# POWER.net
KiCad netlist of a schematic drawn in Altium Designer
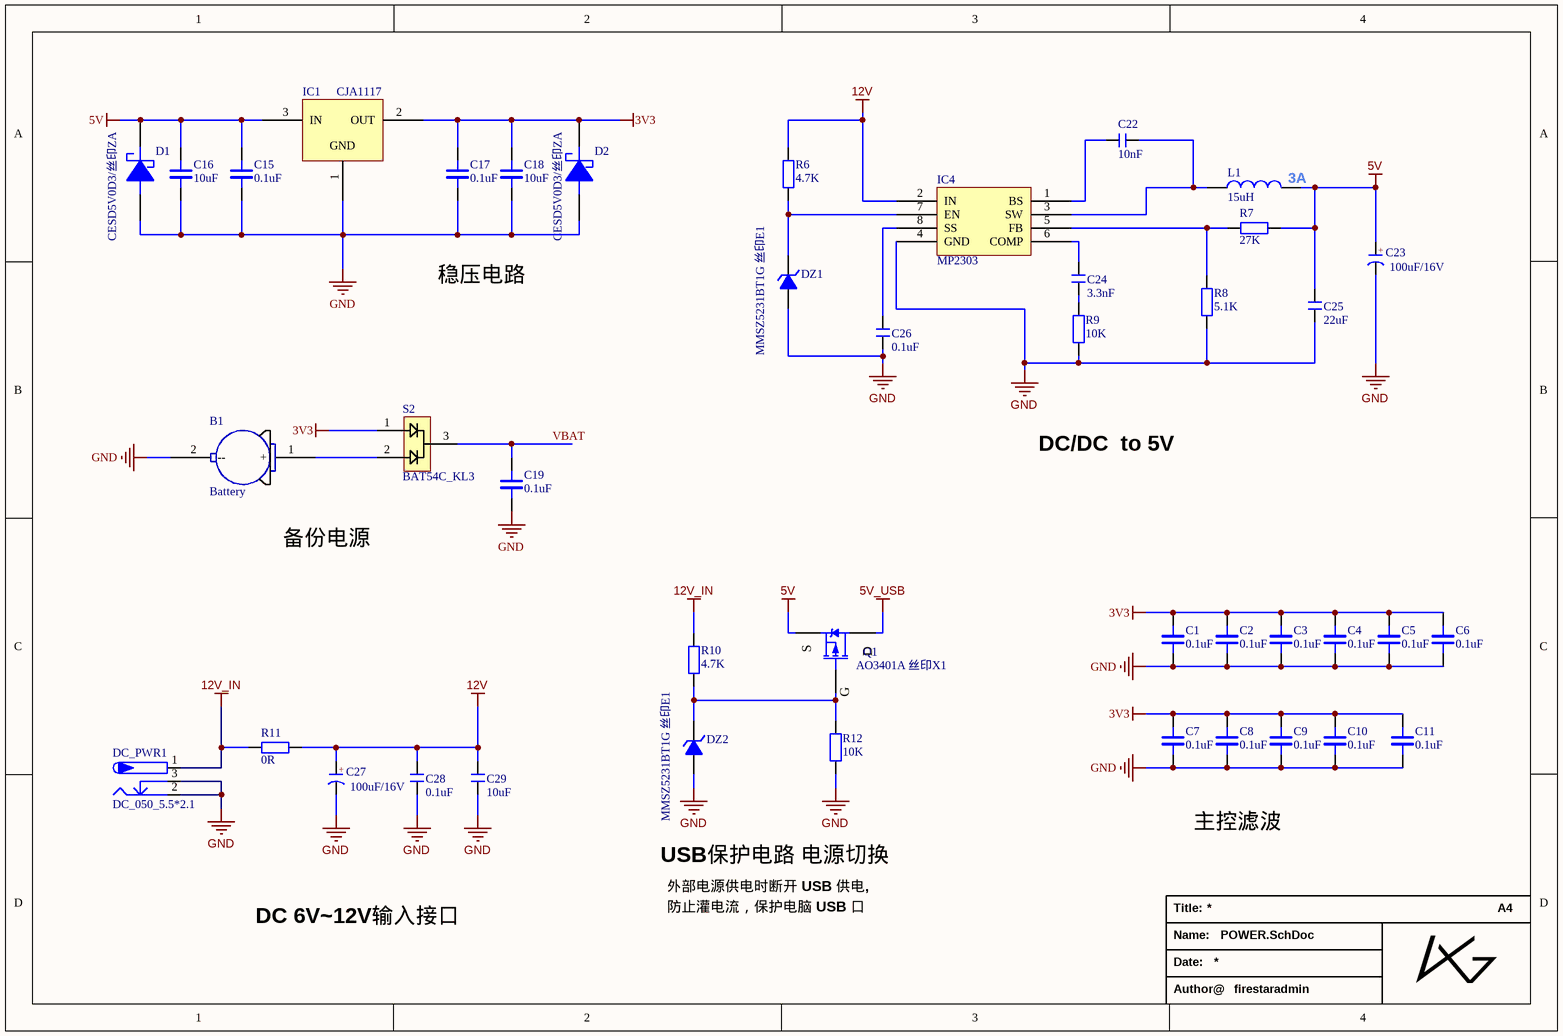
[diagram p0: POWER.SchDoc]

(export (version "E")
  (design (tool "Eeschema 10.0.6"))
  (components
    (comp (ref "B1")
      (value "Battery")
      (footprint "CR1220_B")
      (libsource (lib "altium-import") (part "root_2_Battery_"))
    )
    (comp (ref "C1")
      (value "0.1uF")
      (footprint "C 0603_M")
      (description "Capacitor")
      (libsource (lib "General") (part "CAP"))
    )
    (comp (ref "C2")
      (value "0.1uF")
      (footprint "C 0603_M")
      (description "Capacitor")
      (libsource (lib "General") (part "CAP"))
    )
    (comp (ref "C3")
      (value "0.1uF")
      (footprint "C 0603_M")
      (description "Capacitor")
      (libsource (lib "General") (part "CAP"))
    )
    (comp (ref "C4")
      (value "0.1uF")
      (footprint "C 0603_M")
      (description "Capacitor")
      (libsource (lib "General") (part "CAP"))
    )
    (comp (ref "C5")
      (value "0.1uF")
      (footprint "C 0603_M")
      (description "Capacitor")
      (libsource (lib "General") (part "CAP"))
    )
    (comp (ref "C6")
      (value "0.1uF")
      (footprint "C 0603_M")
      (description "Capacitor")
      (libsource (lib "General") (part "CAP"))
    )
    (comp (ref "C7")
      (value "0.1uF")
      (footprint "C 0603_M")
      (description "Capacitor")
      (libsource (lib "General") (part "CAP"))
    )
    (comp (ref "C8")
      (value "0.1uF")
      (footprint "C 0603_M")
      (description "Capacitor")
      (libsource (lib "General") (part "CAP"))
    )
    (comp (ref "C9")
      (value "0.1uF")
      (footprint "C 0603_M")
      (description "Capacitor")
      (libsource (lib "General") (part "CAP"))
    )
    (comp (ref "C10")
      (value "0.1uF")
      (footprint "C 0603_M")
      (description "Capacitor")
      (libsource (lib "General") (part "CAP"))
    )
    (comp (ref "C11")
      (value "0.1uF")
      (footprint "C 0603_M")
      (description "Capacitor")
      (libsource (lib "General") (part "CAP"))
    )
    (comp (ref "C15")
      (value "0.1uF")
      (footprint "C 0603_M")
      (description "Capacitor")
      (libsource (lib "General") (part "CAP"))
    )
    (comp (ref "C16")
      (value "10uF")
      (footprint "C 0603_M")
      (description "Capacitor")
      (libsource (lib "General") (part "CAP"))
    )
    (comp (ref "C17")
      (value "0.1uF")
      (footprint "C 0603_M")
      (description "Capacitor")
      (libsource (lib "General") (part "CAP"))
    )
    (comp (ref "C18")
      (value "10uF")
      (footprint "C 0603_M")
      (description "Capacitor")
      (libsource (lib "General") (part "CAP"))
    )
    (comp (ref "C19")
      (value "0.1uF")
      (footprint "C 0603_M")
      (description "Capacitor")
      (libsource (lib "General") (part "CAP"))
    )
    (comp (ref "C22")
      (value "10nF")
      (footprint "C 0603_M")
      (description "无极性贴片电容")
      (fields (field (name "版权归属") "源创客"))
      (libsource (lib "altium-import") (part "root_2_C_"))
    )
    (comp (ref "C23")
      (value "100uF/16V")
      (footprint "CM D(6.3*5.4)")
      (description "贴片电解电容")
      (fields (field (name "版权归属") "源创客"))
      (libsource (lib "altium-import") (part "root_3_C-CM_"))
    )
    (comp (ref "C24")
      (value "3.3nF")
      (footprint "C 0603_M")
      (description "无极性贴片电容")
      (fields (field (name "版权归属") "源创客"))
      (libsource (lib "altium-import") (part "root_1_C_"))
    )
    (comp (ref "C25")
      (value "22uF")
      (footprint "C 0603_M")
      (description "无极性贴片电容")
      (fields (field (name "版权归属") "源创客"))
      (libsource (lib "altium-import") (part "root_1_C_"))
    )
    (comp (ref "C26")
      (value "0.1uF")
      (footprint "C 0603_M")
      (description "无极性贴片电容")
      (fields (field (name "版权归属") "源创客"))
      (libsource (lib "altium-import") (part "root_1_C_"))
    )
    (comp (ref "C27")
      (value "100uF/16V")
      (footprint "CM D(6.3*5.4)")
      (description "贴片电解电容")
      (fields (field (name "版权归属") "源创客"))
      (libsource (lib "altium-import") (part "root_3_C-CM_"))
    )
    (comp (ref "C28")
      (value "0.1uF")
      (footprint "C 0603_M")
      (description "无极性贴片电容")
      (fields (field (name "版权归属") "源创客"))
      (libsource (lib "altium-import") (part "root_1_C_"))
    )
    (comp (ref "C29")
      (value "10uF")
      (footprint "C 0603_M")
      (description "无极性贴片电容")
      (fields (field (name "版权归属") "源创客"))
      (libsource (lib "altium-import") (part "root_1_C_"))
    )
    (comp (ref "D1")
      (value "CESD5V0D3/丝印ZA")
      (footprint "SOD-323")
      (libsource (lib "altium-import") (part "root_3_TVS_"))
    )
    (comp (ref "D2")
      (value "CESD5V0D3/丝印ZA")
      (footprint "SOD-323")
      (libsource (lib "altium-import") (part "root_3_TVS_"))
    )
    (comp (ref "DC_PWR1")
      (value "DC_050_5.5*2.1")
      (footprint "DC-050")
      (description "低压电源接口")
      (fields (field (name "版权归属") "源创客"))
      (libsource (lib "altium-import") (part "root_0_mirrored_P-DC_"))
    )
    (comp (ref "DZ1")
      (value "MMSZ5231BT1G 丝印E1")
      (footprint "SOD-123")
      (description "5.1V/0.5W稳压管")
      (fields (field (name "版权归属") "源创客"))
      (libsource (lib "altium-import") (part "root_0_1N4625_"))
    )
    (comp (ref "DZ2")
      (value "MMSZ5231BT1G 丝印E1")
      (footprint "SOD-123")
      (description "5.1V/0.5W稳压管")
      (fields (field (name "版权归属") "源创客"))
      (libsource (lib "altium-import") (part "root_0_1N4625_"))
    )
    (comp (ref "IC1")
      (value "CJA1117")
      (footprint "SOT89_M")
      (libsource (lib "altium-import") (part "root_0_CJA1117_"))
    )
    (comp (ref "IC4")
      (value "MP2303")
      (footprint "SOP8_M")
      (libsource (lib "altium-import") (part "root_0_MP2303_"))
    )
    (comp (ref "L1")
      (value "15uH")
      (footprint "L-SMD-0630")
      (description "小功率贴片电感")
      (fields (field (name "版权归属") "源创客"))
      (libsource (lib "3.1   - 电阻-电容-电感") (part "L"))
    )
    (comp (ref "Q1")
      (value "AO3401A 丝印X1")
      (footprint "SOT23-3M")
      (description "P沟道场效应管")
      (fields (field (name "版权归属") "源创客"))
      (libsource (lib "altium-import") (part "root_1_mirrored_SI2301_"))
    )
    (comp (ref "R6")
      (value "4.7K")
      (footprint "R 0603_M")
      (description "贴片电阻")
      (fields (field (name "版权归属") "源创客"))
      (libsource (lib "altium-import") (part "root_1_R_"))
    )
    (comp (ref "R7")
      (value "27K")
      (footprint "R 0603_M")
      (description "贴片电阻")
      (fields (field (name "版权归属") "源创客"))
      (libsource (lib "altium-import") (part "root_2_R_"))
    )
    (comp (ref "R8")
      (value "5.1K")
      (footprint "R 0603_M")
      (description "贴片电阻")
      (fields (field (name "版权归属") "源创客"))
      (libsource (lib "altium-import") (part "root_1_R_"))
    )
    (comp (ref "R9")
      (value "10K")
      (footprint "R 0603_M")
      (description "贴片电阻")
      (fields (field (name "版权归属") "源创客"))
      (libsource (lib "altium-import") (part "root_1_R_"))
    )
    (comp (ref "R10")
      (value "4.7K")
      (footprint "R 0603_M")
      (description "贴片电阻")
      (fields (field (name "版权归属") "源创客"))
      (libsource (lib "altium-import") (part "root_1_R_"))
    )
    (comp (ref "R11")
      (value "0R")
      (footprint "R 0603_M")
      (description "贴片电阻")
      (fields (field (name "版权归属") "源创客"))
      (libsource (lib "altium-import") (part "root_0_R_"))
    )
    (comp (ref "R12")
      (value "10K")
      (footprint "R 0603_M")
      (description "贴片电阻")
      (fields (field (name "版权归属") "源创客"))
      (libsource (lib "altium-import") (part "root_1_R_"))
    )
    (comp (ref "S2")
      (value "BAT54C_KL3")
      (footprint "SOT23-3M")
      (libsource (lib "altium-import") (part "root_3_BAT54C_KL3_"))
    )
  )
  (nets
    (net (code "1") (name "/VBAT") (class "Default")
      (node (ref "C19") (pin "1") (pinfunction "1_1") (pintype "passive"))
      (node (ref "S2") (pin "3") (pinfunction "3_3") (pintype "passive"))
    )
    (net (code "2") (name "3V3") (class "Default")
      (node (ref "C1") (pin "2") (pinfunction "2_2") (pintype "passive"))
      (node (ref "C10") (pin "2") (pinfunction "2_2") (pintype "passive"))
      (node (ref "C11") (pin "2") (pinfunction "2_2") (pintype "passive"))
      (node (ref "C17") (pin "1") (pinfunction "1_1") (pintype "passive"))
      (node (ref "C18") (pin "1") (pinfunction "1_1") (pintype "passive"))
      (node (ref "C2") (pin "2") (pinfunction "2_2") (pintype "passive"))
      (node (ref "C3") (pin "2") (pinfunction "2_2") (pintype "passive"))
      (node (ref "C4") (pin "2") (pinfunction "2_2") (pintype "passive"))
      (node (ref "C5") (pin "2") (pinfunction "2_2") (pintype "passive"))
      (node (ref "C6") (pin "2") (pinfunction "2_2") (pintype "passive"))
      (node (ref "C7") (pin "2") (pinfunction "2_2") (pintype "passive"))
      (node (ref "C8") (pin "2") (pinfunction "2_2") (pintype "passive"))
      (node (ref "C9") (pin "2") (pinfunction "2_2") (pintype "passive"))
      (node (ref "D2") (pin "2") (pinfunction "-_2") (pintype "passive"))
      (node (ref "IC1") (pin "2") (pinfunction "OUT_2") (pintype "passive"))
      (node (ref "S2") (pin "1") (pintype "passive"))
    )
    (net (code "3") (name "5V") (class "Default")
      (node (ref "C15") (pin "1") (pinfunction "1_1") (pintype "passive"))
      (node (ref "C16") (pin "1") (pinfunction "1_1") (pintype "passive"))
      (node (ref "C23") (pin "1") (pinfunction "A_1") (pintype "passive"))
      (node (ref "C25") (pin "2") (pinfunction "2_2") (pintype "passive"))
      (node (ref "D1") (pin "2") (pinfunction "-_2") (pintype "passive"))
      (node (ref "IC1") (pin "3") (pinfunction "IN_3") (pintype "passive"))
      (node (ref "L1") (pin "2") (pinfunction "2_2") (pintype "passive"))
      (node (ref "Q1") (pin "2") (pinfunction "S_2") (pintype "passive"))
      (node (ref "R7") (pin "1") (pinfunction "1_1") (pintype "passive"))
    )
    (net (code "4") (name "5V_USB") (class "Default")
      (node (ref "Q1") (pin "3") (pinfunction "D_3") (pintype "passive"))
    )
    (net (code "5") (name "12V") (class "Default")
      (node (ref "C27") (pin "1") (pinfunction "A_1") (pintype "passive"))
      (node (ref "C28") (pin "2") (pinfunction "2_2") (pintype "passive"))
      (node (ref "C29") (pin "2") (pinfunction "2_2") (pintype "passive"))
      (node (ref "IC4") (pin "2") (pinfunction "IN_2") (pintype "passive"))
      (node (ref "R11") (pin "2") (pinfunction "2_2") (pintype "passive"))
      (node (ref "R6") (pin "2") (pinfunction "2_2") (pintype "passive"))
    )
    (net (code "6") (name "12V_IN") (class "Default")
      (node (ref "DC_PWR1") (pin "1") (pintype "power_in"))
      (node (ref "R10") (pin "2") (pinfunction "2_2") (pintype "passive"))
      (node (ref "R11") (pin "1") (pinfunction "1_1") (pintype "passive"))
    )
    (net (code "7") (name "GND") (class "Default")
      (node (ref "B1") (pin "2") (pinfunction "--_2") (pintype "passive"))
      (node (ref "C1") (pin "1") (pinfunction "1_1") (pintype "passive"))
      (node (ref "C10") (pin "1") (pinfunction "1_1") (pintype "passive"))
      (node (ref "C11") (pin "1") (pinfunction "1_1") (pintype "passive"))
      (node (ref "C15") (pin "2") (pinfunction "2_2") (pintype "passive"))
      (node (ref "C16") (pin "2") (pinfunction "2_2") (pintype "passive"))
      (node (ref "C17") (pin "2") (pinfunction "2_2") (pintype "passive"))
      (node (ref "C18") (pin "2") (pinfunction "2_2") (pintype "passive"))
      (node (ref "C19") (pin "2") (pinfunction "2_2") (pintype "passive"))
      (node (ref "C2") (pin "1") (pinfunction "1_1") (pintype "passive"))
      (node (ref "C23") (pin "2") (pinfunction "K_2") (pintype "passive"))
      (node (ref "C25") (pin "1") (pinfunction "1_1") (pintype "passive"))
      (node (ref "C26") (pin "1") (pinfunction "1_1") (pintype "passive"))
      (node (ref "C27") (pin "2") (pinfunction "K_2") (pintype "passive"))
      (node (ref "C28") (pin "1") (pinfunction "1_1") (pintype "passive"))
      (node (ref "C29") (pin "1") (pinfunction "1_1") (pintype "passive"))
      (node (ref "C3") (pin "1") (pinfunction "1_1") (pintype "passive"))
      (node (ref "C4") (pin "1") (pinfunction "1_1") (pintype "passive"))
      (node (ref "C5") (pin "1") (pinfunction "1_1") (pintype "passive"))
      (node (ref "C6") (pin "1") (pinfunction "1_1") (pintype "passive"))
      (node (ref "C7") (pin "1") (pinfunction "1_1") (pintype "passive"))
      (node (ref "C8") (pin "1") (pinfunction "1_1") (pintype "passive"))
      (node (ref "C9") (pin "1") (pinfunction "1_1") (pintype "passive"))
      (node (ref "D1") (pin "1") (pinfunction "+_1") (pintype "passive"))
      (node (ref "D2") (pin "1") (pinfunction "+_1") (pintype "passive"))
      (node (ref "DC_PWR1") (pin "2") (pintype "power_in"))
      (node (ref "DC_PWR1") (pin "3") (pintype "power_in"))
      (node (ref "DZ1") (pin "1") (pinfunction "A_1") (pintype "passive"))
      (node (ref "DZ2") (pin "1") (pinfunction "A_1") (pintype "passive"))
      (node (ref "IC1") (pin "1") (pinfunction "GND_1") (pintype "passive"))
      (node (ref "IC4") (pin "4") (pinfunction "GND_4") (pintype "passive"))
      (node (ref "R12") (pin "1") (pinfunction "1_1") (pintype "passive"))
      (node (ref "R8") (pin "1") (pinfunction "1_1") (pintype "passive"))
      (node (ref "R9") (pin "1") (pinfunction "1_1") (pintype "passive"))
    )
    (net (code "8") (name "Net-(B1-+)") (class "Default")
      (node (ref "B1") (pin "1") (pinfunction "+_1") (pintype "passive"))
      (node (ref "S2") (pin "2") (pinfunction "2_2") (pintype "passive"))
    )
    (net (code "9") (name "Net-(C24-Pad1)") (class "Default")
      (node (ref "C24") (pin "1") (pinfunction "1_1") (pintype "passive"))
      (node (ref "R9") (pin "2") (pinfunction "2_2") (pintype "passive"))
    )
    (net (code "10") (name "Net-(DZ1-K)") (class "Default")
      (node (ref "DZ1") (pin "2") (pinfunction "K_2") (pintype "passive"))
      (node (ref "IC4") (pin "7") (pinfunction "EN_7") (pintype "passive"))
      (node (ref "R6") (pin "1") (pinfunction "1_1") (pintype "passive"))
    )
    (net (code "11") (name "Net-(DZ2-K)") (class "Default")
      (node (ref "DZ2") (pin "2") (pinfunction "K_2") (pintype "passive"))
      (node (ref "Q1") (pin "1") (pinfunction "G_1") (pintype "passive"))
      (node (ref "R10") (pin "1") (pinfunction "1_1") (pintype "passive"))
      (node (ref "R12") (pin "2") (pinfunction "2_2") (pintype "passive"))
    )
    (net (code "12") (name "Net-(IC4-BS)") (class "Default")
      (node (ref "C22") (pin "2") (pinfunction "2_2") (pintype "passive"))
      (node (ref "IC4") (pin "1") (pinfunction "BS_1") (pintype "passive"))
    )
    (net (code "13") (name "Net-(IC4-COMP)") (class "Default")
      (node (ref "C24") (pin "2") (pinfunction "2_2") (pintype "passive"))
      (node (ref "IC4") (pin "6") (pinfunction "COMP_6") (pintype "passive"))
    )
    (net (code "14") (name "Net-(IC4-FB)") (class "Default")
      (node (ref "IC4") (pin "5") (pinfunction "FB_5") (pintype "passive"))
      (node (ref "R7") (pin "2") (pinfunction "2_2") (pintype "passive"))
      (node (ref "R8") (pin "2") (pinfunction "2_2") (pintype "passive"))
    )
    (net (code "15") (name "Net-(IC4-SS)") (class "Default")
      (node (ref "C26") (pin "2") (pinfunction "2_2") (pintype "passive"))
      (node (ref "IC4") (pin "8") (pinfunction "SS_8") (pintype "passive"))
    )
    (net (code "16") (name "Net-(IC4-SW)") (class "Default")
      (node (ref "C22") (pin "1") (pinfunction "1_1") (pintype "passive"))
      (node (ref "IC4") (pin "3") (pinfunction "SW_3") (pintype "passive"))
      (node (ref "L1") (pin "1") (pinfunction "1_1") (pintype "passive"))
    )
  )
)
